# FMC_Delay_1ns_4Cha.net
KiCad netlist of a schematic drawn in Altium Designer
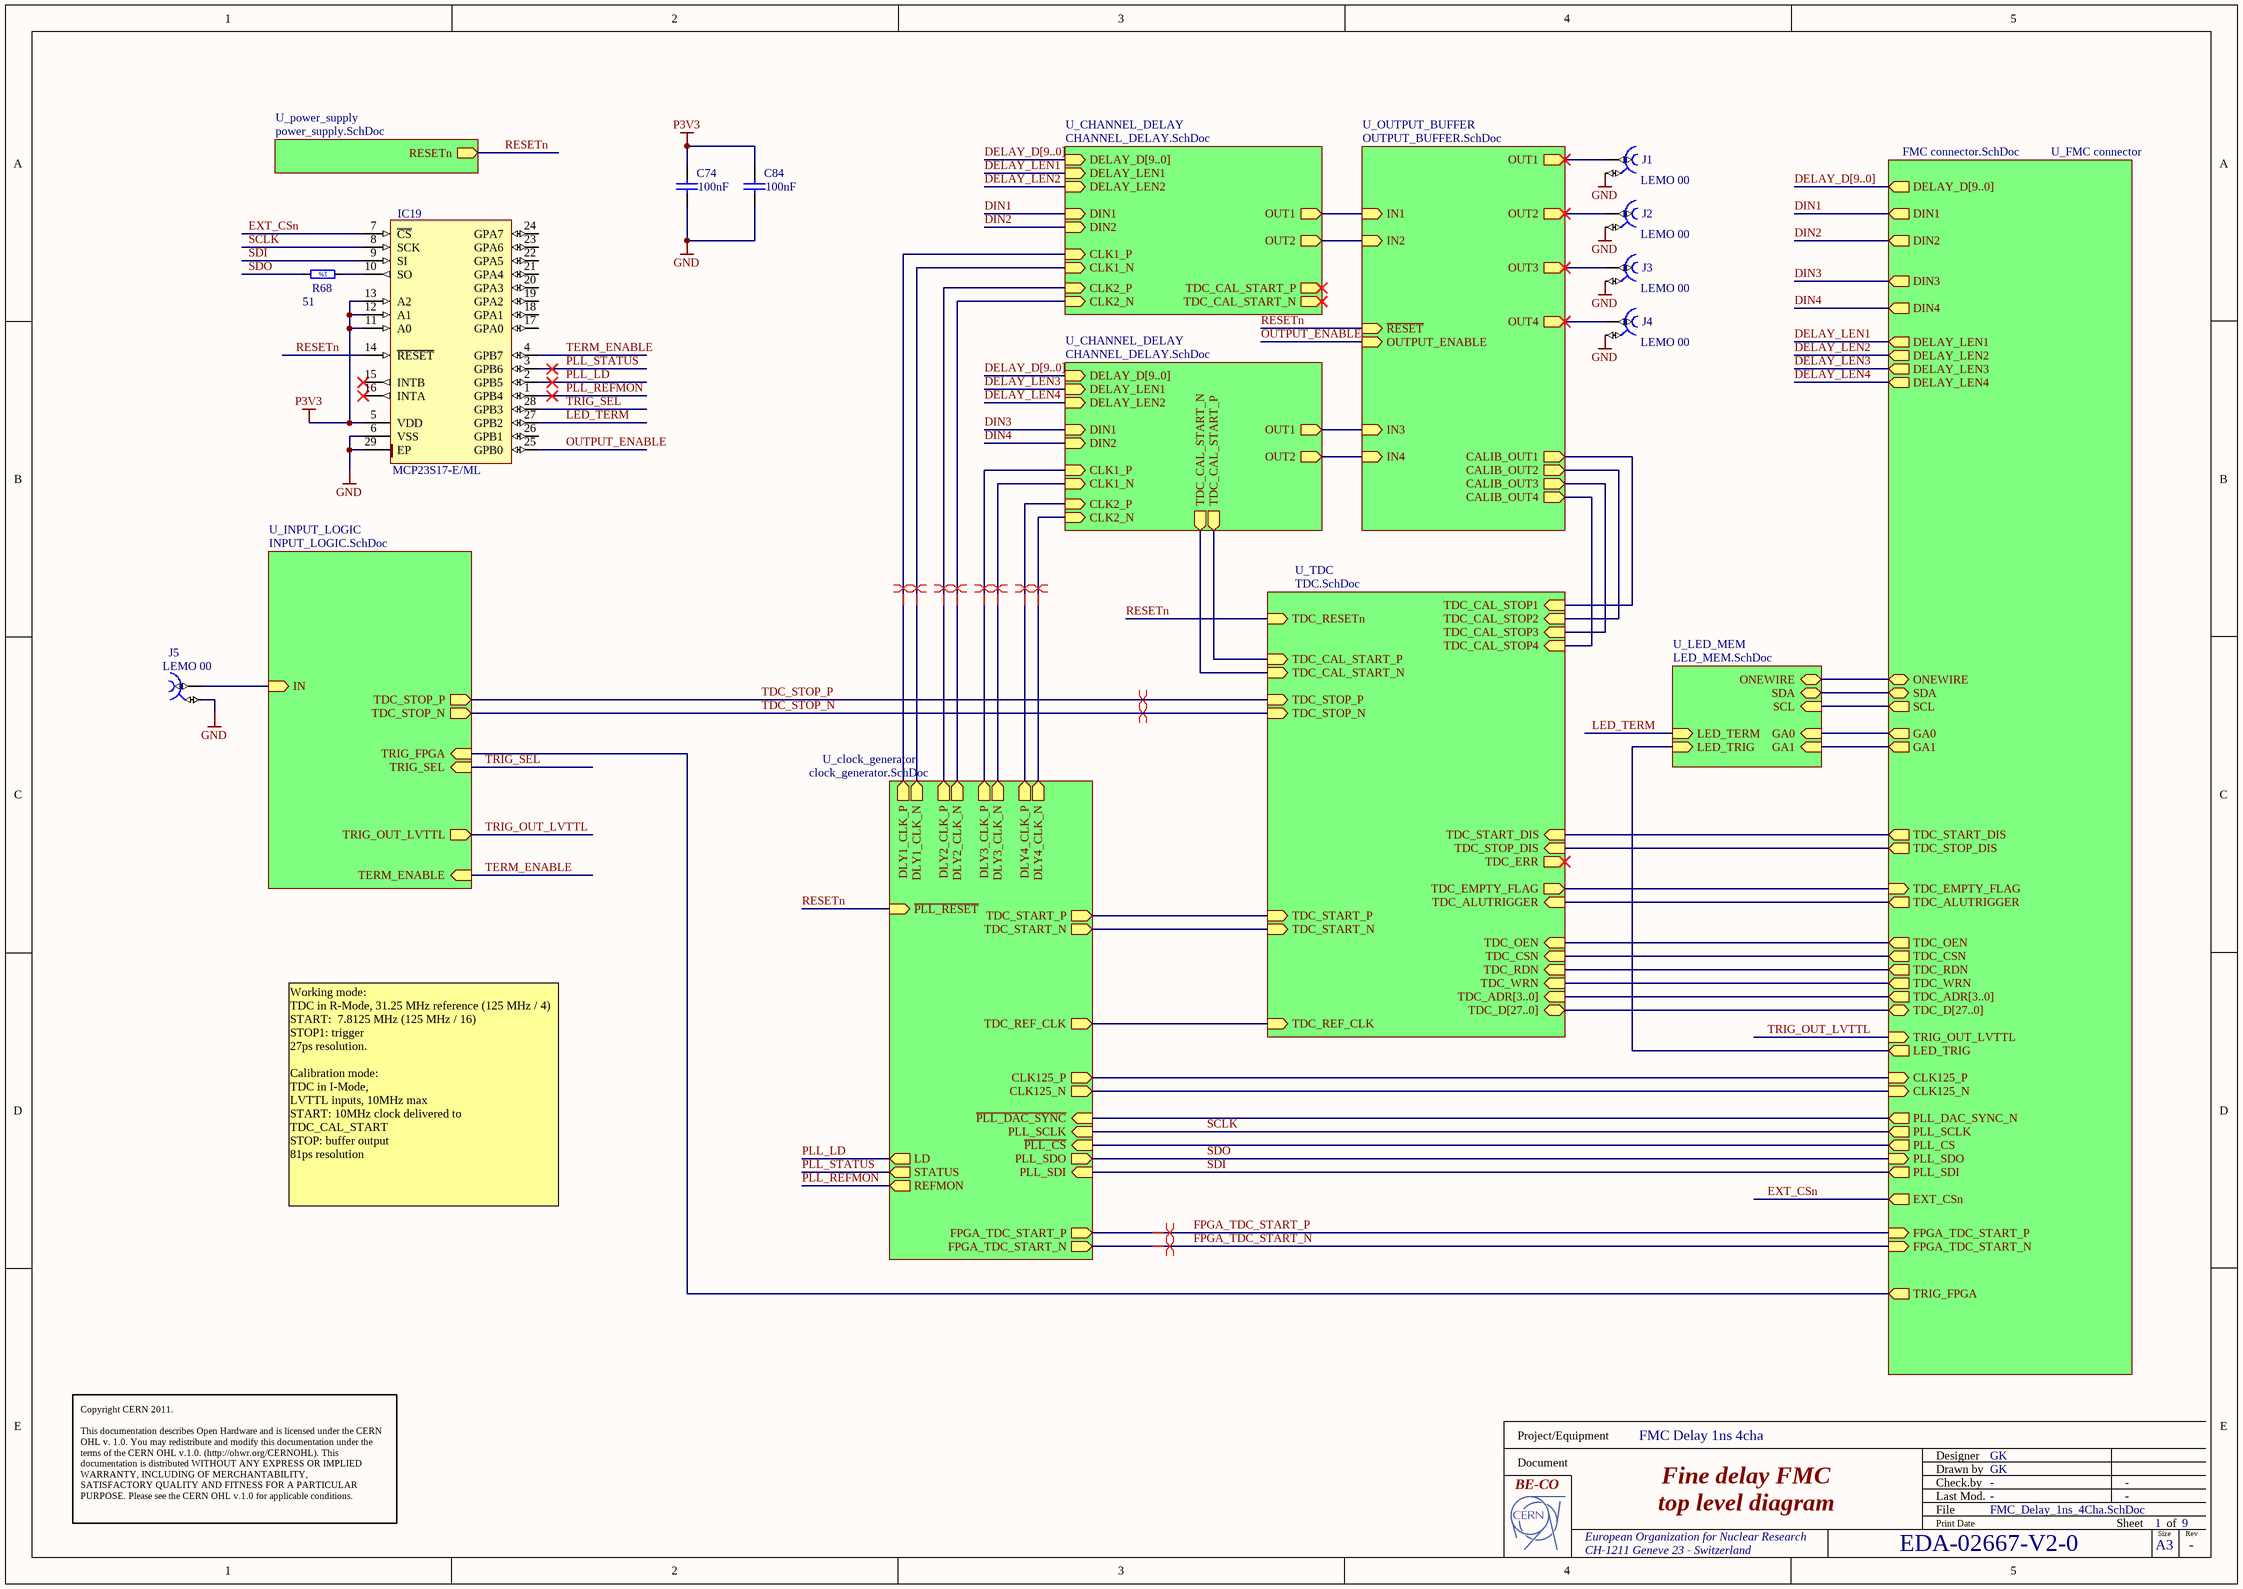
[diagram p0: FMC_Delay_1ns_4Cha.SchDoc]

(export (version "E")
  (design (tool "Eeschema 10.0.6"))
  (components
    (comp (ref "C74")
      (value "100nF")
      (footprint "CAPC1608X87N")
      (description "Non-polarised capacitor")
      (fields
        (field (name "MANUFACTURER1 PART NUMBER") "223858615649")
        (field (name "MANUFACTURER") "GENERIC")
        (field (name "AUTHOR") "CERN DEM JLC")
      )
      (libsource (lib "Capacitors") (part "Capacitor - non polarized"))
    )
    (comp (ref "C84")
      (value "100nF")
      (footprint "CAPC1608X87N")
      (description "Non-polarised capacitor")
      (fields
        (field (name "MANUFACTURER1 PART NUMBER") "223858615649")
        (field (name "MANUFACTURER") "GENERIC")
        (field (name "AUTHOR") "CERN DEM JLC")
      )
      (libsource (lib "Capacitors") (part "Capacitor - non polarized"))
    )
    (comp (ref "IC19")
      (value "MCP23S17-E/ML")
      (footprint "QFN65P600X600X100-29N-S420")
      (description "16-bit I/O Port Expander With Serial Interface")
      (fields (field (name "MANUFACTURER") "MICROCHIP TECHNOLOGY") (field (name "AUTHOR") "CERN DEM JLC"))
      (libsource (lib "ICs And Semiconductors") (part "MCP23S17-E/ML"))
    )
    (comp (ref "J1")
      (value "LEMO 00")
      (footprint "LEMO_EPL.00.250.NTN")
      (fields
        (field (name "PART NUMBER") "LEMO_EPL.00.250.NTN")
        (field (name "MANUFACTURER") "LEMO")
        (field (name "MANUFACTURER PART NUMBER") "EPL.00.250.NTN")
        (field (name "AUTHOR") "CERN DEM JLC")
      )
      (libsource (lib "Connectors") (part "Coax_1Female_1Shield"))
    )
    (comp (ref "J2")
      (value "LEMO 00")
      (footprint "LEMO_EPL.00.250.NTN")
      (fields
        (field (name "PART NUMBER") "LEMO_EPL.00.250.NTN")
        (field (name "MANUFACTURER") "LEMO")
        (field (name "MANUFACTURER PART NUMBER") "EPL.00.250.NTN")
        (field (name "AUTHOR") "CERN DEM JLC")
      )
      (libsource (lib "Connectors") (part "Coax_1Female_1Shield"))
    )
    (comp (ref "J3")
      (value "LEMO 00")
      (footprint "LEMO_EPL.00.250.NTN")
      (fields
        (field (name "PART NUMBER") "LEMO_EPL.00.250.NTN")
        (field (name "MANUFACTURER") "LEMO")
        (field (name "MANUFACTURER PART NUMBER") "EPL.00.250.NTN")
        (field (name "AUTHOR") "CERN DEM JLC")
      )
      (libsource (lib "Connectors") (part "Coax_1Female_1Shield"))
    )
    (comp (ref "J4")
      (value "LEMO 00")
      (footprint "LEMO_EPL.00.250.NTN")
      (fields
        (field (name "PART NUMBER") "LEMO_EPL.00.250.NTN")
        (field (name "MANUFACTURER") "LEMO")
        (field (name "MANUFACTURER PART NUMBER") "EPL.00.250.NTN")
        (field (name "AUTHOR") "CERN DEM JLC")
      )
      (libsource (lib "Connectors") (part "Coax_1Female_1Shield"))
    )
    (comp (ref "J5")
      (value "LEMO 00")
      (footprint "LEMO_EPL.00.250.NTN")
      (fields
        (field (name "PART NUMBER") "LEMO_EPL.00.250.NTN")
        (field (name "MANUFACTURER") "LEMO")
        (field (name "MANUFACTURER PART NUMBER") "EPL.00.250.NTN")
        (field (name "AUTHOR") "CERN DEM JLC")
      )
      (libsource (lib "") (part "Coax_1Female_1Shield_1"))
    )
    (comp (ref "R68")
      (value "51")
      (footprint "RESC1608X55N")
      (description "Resistor - 1%")
      (fields
        (field (name "PART NUMBER") "R0603_51R_1%_0.1W_100PPM")
        (field (name "POWER") "0.1W")
        (field (name "AUTHOR") "CERN DEM JLC")
      )
      (libsource (lib "Resistors") (part "Resistor - 1%"))
    )
  )
  (nets
    (net (code "34") (name "/EXT_CSn") (class "Default")
      (node (ref "IC19") (pin "7") (pinfunction "~{CS}_7") (pintype "input"))
    )
    (net (code "39") (name "/IN") (class "Default")
      (node (ref "J5") (pin "1") (pinfunction "1_1") (pintype "bidirectional"))
    )
    (net (code "40") (name "/LED_TERM") (class "Default")
      (node (ref "IC19") (pin "27") (pinfunction "GPB2_27") (pintype "bidirectional"))
    )
    (net (code "43") (name "/OUT1") (class "Default")
      (node (ref "J1") (pin "1") (pinfunction "1_1") (pintype "bidirectional+no_connect"))
    )
    (net (code "46") (name "/OUT2") (class "Default")
      (node (ref "J2") (pin "1") (pinfunction "1_1") (pintype "bidirectional+no_connect"))
    )
    (net (code "49") (name "/OUT3") (class "Default")
      (node (ref "J3") (pin "1") (pinfunction "1_1") (pintype "bidirectional+no_connect"))
    )
    (net (code "50") (name "/OUT4") (class "Default")
      (node (ref "J4") (pin "1") (pinfunction "1_1") (pintype "bidirectional+no_connect"))
    )
    (net (code "51") (name "/OUTPUT_ENABLE") (class "Default")
      (node (ref "IC19") (pin "25") (pinfunction "GPB0_25") (pintype "bidirectional"))
    )
    (net (code "54") (name "/PLL_LD") (class "Default")
      (node (ref "IC19") (pin "2") (pinfunction "GPB5_2") (pintype "bidirectional"))
    )
    (net (code "55") (name "/PLL_REFMON") (class "Default")
      (node (ref "IC19") (pin "1") (pinfunction "GPB4_1") (pintype "bidirectional"))
    )
    (net (code "56") (name "/PLL_STATUS") (class "Default")
      (node (ref "IC19") (pin "3") (pinfunction "GPB6_3") (pintype "bidirectional"))
    )
    (net (code "57") (name "/RESETn") (class "Default")
      (node (ref "IC19") (pin "14") (pinfunction "~{RESET}_14") (pintype "input"))
    )
    (net (code "59") (name "/SCLK") (class "Default")
      (node (ref "IC19") (pin "8") (pinfunction "SCK_8") (pintype "input"))
    )
    (net (code "61") (name "/SDI") (class "Default")
      (node (ref "IC19") (pin "9") (pinfunction "SI_9") (pintype "input"))
    )
    (net (code "62") (name "/SDO") (class "Default")
      (node (ref "R68") (pin "2") (pinfunction "2_2") (pintype "passive"))
    )
    (net (code "83") (name "/TERM_ENABLE") (class "Default")
      (node (ref "IC19") (pin "4") (pinfunction "GPB7_4") (pintype "bidirectional"))
    )
    (net (code "86") (name "/TRIG_SEL") (class "Default")
      (node (ref "IC19") (pin "28") (pinfunction "GPB3_28") (pintype "bidirectional"))
    )
    (net (code "87") (name "GND") (class "Default")
      (node (ref "C74") (pin "2") (pinfunction "2_2") (pintype "passive"))
      (node (ref "C84") (pin "2") (pinfunction "2_2") (pintype "passive"))
      (node (ref "IC19") (pin "29") (pinfunction "EP_29") (pintype "power_in"))
      (node (ref "IC19") (pin "6") (pinfunction "VSS_6") (pintype "power_in"))
      (node (ref "J1") (pin "2") (pinfunction "2_2") (pintype "bidirectional"))
      (node (ref "J2") (pin "2") (pinfunction "2_2") (pintype "bidirectional"))
      (node (ref "J3") (pin "2") (pinfunction "2_2") (pintype "bidirectional"))
      (node (ref "J4") (pin "2") (pinfunction "2_2") (pintype "bidirectional"))
      (node (ref "J5") (pin "2") (pinfunction "2_2") (pintype "bidirectional"))
    )
    (net (code "88") (name "Net-(IC19-SO)") (class "Default")
      (node (ref "IC19") (pin "10") (pinfunction "SO_10") (pintype "output"))
      (node (ref "R68") (pin "1") (pinfunction "1_1") (pintype "passive"))
    )
    (net (code "89") (name "P3V3") (class "Default")
      (node (ref "C74") (pin "1") (pinfunction "1_1") (pintype "passive"))
      (node (ref "C84") (pin "1") (pinfunction "1_1") (pintype "passive"))
      (node (ref "IC19") (pin "11") (pinfunction "A0_11") (pintype "input"))
      (node (ref "IC19") (pin "12") (pinfunction "A1_12") (pintype "input"))
      (node (ref "IC19") (pin "13") (pinfunction "A2_13") (pintype "input"))
      (node (ref "IC19") (pin "5") (pinfunction "VDD_5") (pintype "power_in"))
    )
    (net (code "90") (name "unconnected-(IC19-GPA0-Pad17)") (class "Default")
      (node (ref "IC19") (pin "17") (pinfunction "GPA0_17") (pintype "bidirectional"))
    )
    (net (code "91") (name "unconnected-(IC19-GPA1-Pad18)") (class "Default")
      (node (ref "IC19") (pin "18") (pinfunction "GPA1_18") (pintype "bidirectional"))
    )
    (net (code "92") (name "unconnected-(IC19-GPA2-Pad19)") (class "Default")
      (node (ref "IC19") (pin "19") (pinfunction "GPA2_19") (pintype "bidirectional"))
    )
    (net (code "93") (name "unconnected-(IC19-GPA3-Pad20)") (class "Default")
      (node (ref "IC19") (pin "20") (pinfunction "GPA3_20") (pintype "bidirectional"))
    )
    (net (code "94") (name "unconnected-(IC19-GPA4-Pad21)") (class "Default")
      (node (ref "IC19") (pin "21") (pinfunction "GPA4_21") (pintype "bidirectional"))
    )
    (net (code "95") (name "unconnected-(IC19-GPA5-Pad22)") (class "Default")
      (node (ref "IC19") (pin "22") (pinfunction "GPA5_22") (pintype "bidirectional"))
    )
    (net (code "96") (name "unconnected-(IC19-GPA6-Pad23)") (class "Default")
      (node (ref "IC19") (pin "23") (pinfunction "GPA6_23") (pintype "bidirectional"))
    )
    (net (code "97") (name "unconnected-(IC19-GPA7-Pad24)") (class "Default")
      (node (ref "IC19") (pin "24") (pinfunction "GPA7_24") (pintype "bidirectional"))
    )
    (net (code "98") (name "unconnected-(IC19-GPB1-Pad26)") (class "Default")
      (node (ref "IC19") (pin "26") (pinfunction "GPB1_26") (pintype "bidirectional"))
    )
    (net (code "99") (name "unconnected-(IC19-INTA-Pad16)") (class "Default")
      (node (ref "IC19") (pin "16") (pinfunction "INTA_16") (pintype "output+no_connect"))
    )
    (net (code "100") (name "unconnected-(IC19-INTB-Pad15)") (class "Default")
      (node (ref "IC19") (pin "15") (pinfunction "INTB_15") (pintype "output+no_connect"))
    )
  )
)
